# ESQUEMATICOS2.net
KiCad netlist of a schematic drawn in Altium Designer
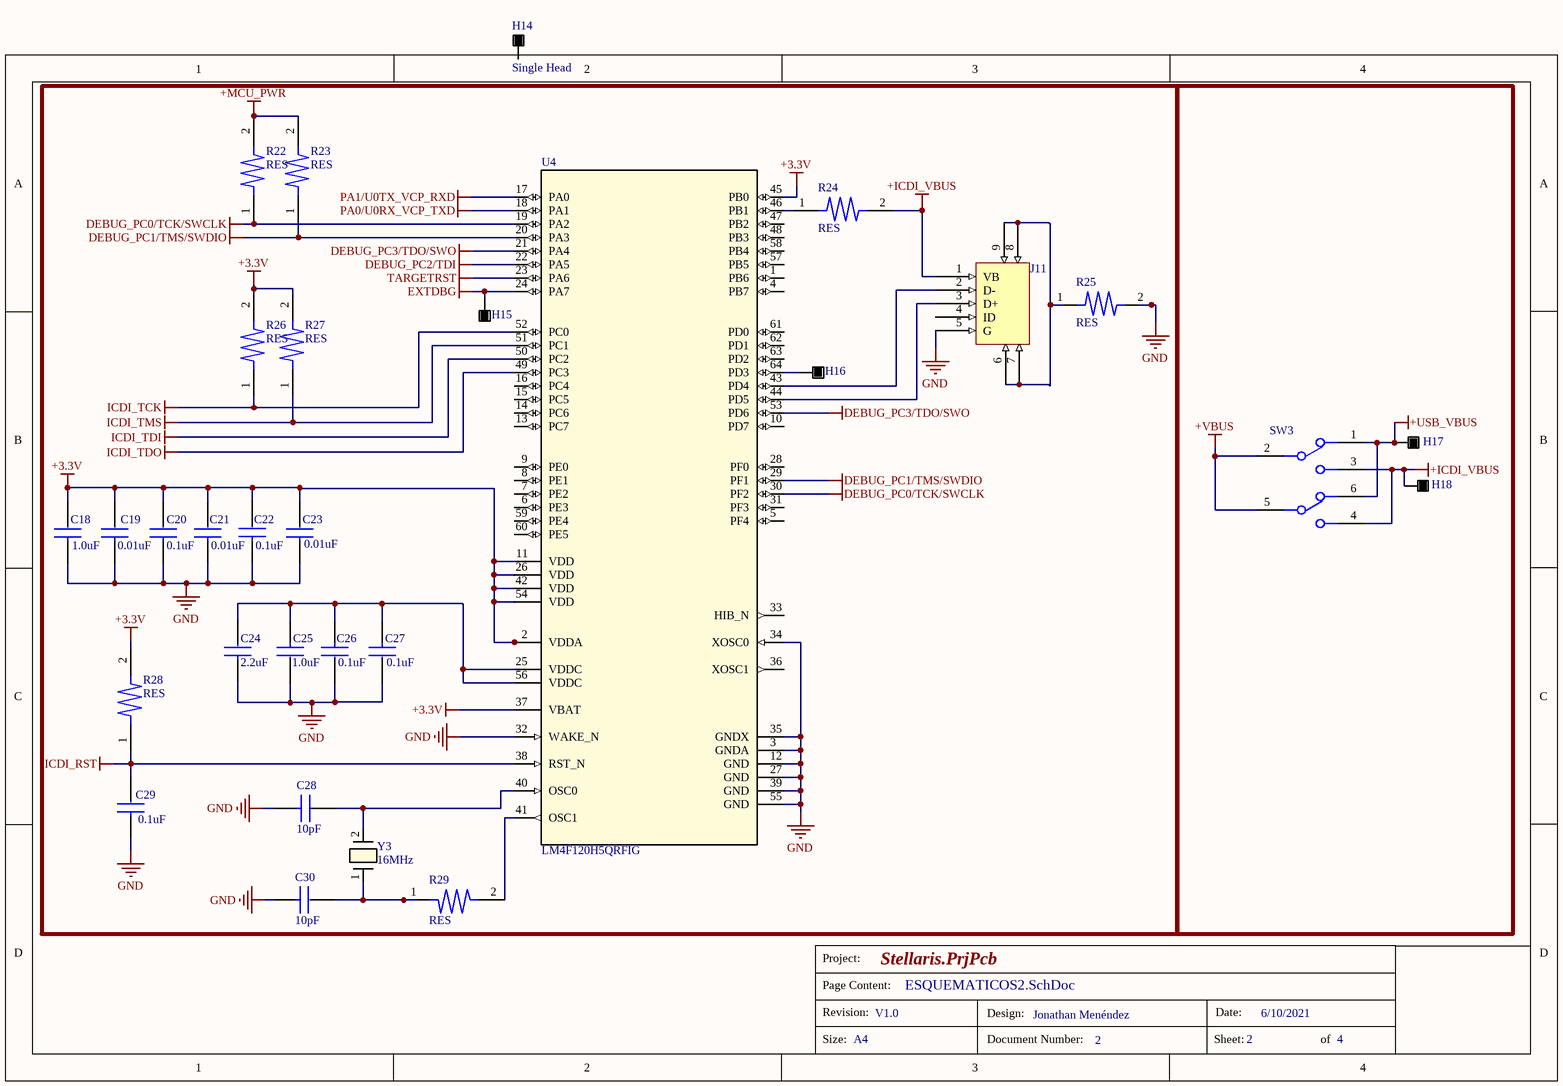
[diagram p0: ESQUEMATICOS2.SchDoc]

(export (version "E")
  (design (tool "Eeschema 10.0.6"))
  (components
    (comp (ref "C18")
      (value "1.0uF")
      (footprint "CAP 0402")
      (description "0402 0.1 uF 16 V ±10% Tolerance X7R Multilayer Ceramic Chip Capacitor")
      (fields
        (field (name "MANUFACTURER") "Taiyo Yuden")
        (field (name "MANUFACTURER PART NUMBER") "EMK105B7104KV-F")
      )
      (libsource (lib "Lib_componentes_Stellaris") (part "EMK105B7104KV-F"))
    )
    (comp (ref "C19")
      (value "0.01uF")
      (footprint "CAP 0402")
      (description "0402 0.01 uF 25 V ±10% X7R Automotive Multilayer Ceramic Capacitor")
      (fields
        (field (name "MANUFACTURER") "Taiyo Yuden")
        (field (name "MANUFACTURER PART NUMBER") "TMK105B7103KV-F")
      )
      (libsource (lib "Lib_componentes_Stellaris") (part "TMK105B7103KV-F"))
    )
    (comp (ref "C20")
      (value "0.1uF")
      (footprint "CAP 0402")
      (description "0402 0.1 uF 16 V ±10% Tolerance X7R Multilayer Ceramic Chip Capacitor")
      (fields
        (field (name "MANUFACTURER") "Taiyo Yuden")
        (field (name "MANUFACTURER PART NUMBER") "EMK105B7104KV-F")
      )
      (libsource (lib "Lib_componentes_Stellaris") (part "EMK105B7104KV-F"))
    )
    (comp (ref "C21")
      (value "0.01uF")
      (footprint "CAP 0402")
      (description "0402 0.01 uF 25 V ±10% X7R Automotive Multilayer Ceramic Capacitor")
      (fields
        (field (name "MANUFACTURER") "Taiyo Yuden")
        (field (name "MANUFACTURER PART NUMBER") "TMK105B7103KV-F")
      )
      (libsource (lib "Lib_componentes_Stellaris") (part "TMK105B7103KV-F"))
    )
    (comp (ref "C22")
      (value "0.1uF")
      (footprint "CAP 0402")
      (description "0402 0.1 uF 16 V ±10% Tolerance X7R Multilayer Ceramic Chip Capacitor")
      (fields
        (field (name "MANUFACTURER") "Taiyo Yuden")
        (field (name "MANUFACTURER PART NUMBER") "EMK105B7104KV-F")
      )
      (libsource (lib "Lib_componentes_Stellaris") (part "EMK105B7104KV-F"))
    )
    (comp (ref "C23")
      (value "0.01uF")
      (footprint "CAP 0402")
      (description "0402 0.01 uF 25 V ±10% X7R Automotive Multilayer Ceramic Capacitor")
      (fields
        (field (name "MANUFACTURER") "Taiyo Yuden")
        (field (name "MANUFACTURER PART NUMBER") "TMK105B7103KV-F")
      )
      (libsource (lib "Lib_componentes_Stellaris") (part "TMK105B7103KV-F"))
    )
    (comp (ref "C24")
      (value "2.2uF")
      (description "0603 2.2 uF 16 V ±10% Tolerance X5R SMT Multilayer Ceramic Capacitor")
      (fields
        (field (name "MANUFACTURER") "Murata")
        (field (name "MANUFACTURER PART NUMBER") "GRM188R61C225KE15D")
      )
      (libsource (lib "Lib_componentes_Stellaris") (part "GRM188R61C225KE15D"))
    )
    (comp (ref "C25")
      (value "1.0uF")
      (footprint "CAP 0402")
      (description "Multilayer Ceramic Capacitor, Tanceram Series, 1 - F, - 10%, X5R, 10 V, 0402 [1005 Metric]")
      (fields
        (field (name "MANUFACTURER") "Johanson")
        (field (name "MANUFACTURER PART NUMBER") "100R07X105KV4T")
      )
      (libsource (lib "Lib_componentes_Stellaris") (part "100R07X105KV4T"))
    )
    (comp (ref "C26")
      (value "0.1uF")
      (footprint "CAP 0402")
      (description "0402 0.1 uF 16 V ±10% Tolerance X7R Multilayer Ceramic Chip Capacitor")
      (fields
        (field (name "MANUFACTURER") "Taiyo Yuden")
        (field (name "MANUFACTURER PART NUMBER") "EMK105B7104KV-F")
      )
      (libsource (lib "Lib_componentes_Stellaris") (part "EMK105B7104KV-F"))
    )
    (comp (ref "C27")
      (value "0.1uF")
      (footprint "CAP 0402")
      (description "0402 0.1 uF 16 V ±10% Tolerance X7R Multilayer Ceramic Chip Capacitor")
      (fields
        (field (name "MANUFACTURER") "Taiyo Yuden")
        (field (name "MANUFACTURER PART NUMBER") "EMK105B7104KV-F")
      )
      (libsource (lib "Lib_componentes_Stellaris") (part "EMK105B7104KV-F"))
    )
    (comp (ref "C28")
      (value "10pF")
      (footprint "CAP 0402")
      (description "Cap Ceramic 10pF 50V C0G 5% SMD 0402 125°C Paper T/R")
      (fields
        (field (name "MANUFACTURER") "Murata")
        (field (name "MANUFACTURER PART NUMBER") "GRM1555C1H100JZ01D")
      )
      (libsource (lib "Lib_componentes_Stellaris") (part "GRM1555C1H100JZ01D"))
    )
    (comp (ref "C29")
      (value "0.1uF")
      (footprint "CAP 0402")
      (description "0402 0.1 uF 16 V ±10% Tolerance X7R Multilayer Ceramic Chip Capacitor")
      (fields
        (field (name "MANUFACTURER") "Taiyo Yuden")
        (field (name "MANUFACTURER PART NUMBER") "EMK105B7104KV-F")
      )
      (libsource (lib "Lib_componentes_Stellaris") (part "EMK105B7104KV-F"))
    )
    (comp (ref "C30")
      (value "10pF")
      (footprint "CAP 0402")
      (description "Cap Ceramic 10pF 50V C0G 5% SMD 0402 125°C Paper T/R")
      (fields
        (field (name "MANUFACTURER") "Murata")
        (field (name "MANUFACTURER PART NUMBER") "GRM1555C1H100JZ01D")
      )
      (libsource (lib "Lib_componentes_Stellaris") (part "GRM1555C1H100JZ01D"))
    )
    (comp (ref "H14")
      (value "Single Head")
      (footprint "Connector")
      (description "Connector")
      (libsource (lib "Lib_componentes_Stellaris") (part "Single Head"))
    )
    (comp (ref "H15")
      (value "Single Head")
      (footprint "Connector")
      (description "Connector")
      (libsource (lib "") (part "Single Head_2"))
    )
    (comp (ref "H16")
      (value "Single Head")
      (footprint "Connector")
      (description "Connector")
      (libsource (lib "") (part "Single Head_1"))
    )
    (comp (ref "H17")
      (value "Single Head")
      (footprint "Connector")
      (description "Connector")
      (libsource (lib "") (part "Single Head_1"))
    )
    (comp (ref "H18")
      (value "Single Head")
      (footprint "Connector")
      (description "Connector")
      (libsource (lib "") (part "Single Head_1"))
    )
    (comp (ref "J11")
      (value "ZX62-B-5PA(11)")
      (footprint "Micro USB 2.0 Type B")
      (description "Conn Micro USB 2.0 Type B RCP 5 POS 0.65mm Solder RA SMD 5 Terminal 1 Port T/R")
      (fields (field (name "MANUFACTURER") "Hirose"))
      (libsource (lib "Lib_componentes_Stellaris") (part "ZX62-B-5PA(11)"))
    )
    (comp (ref "R22")
      (value "RES")
      (footprint "RES 0402")
      (description "Res General Purpose Thick Film 0402 10K Ohm 1% 1/16W ±100ppm/°C Molded SMD Paper T/R")
      (fields
        (field (name "MANUFACTURER") "Yageo")
        (field (name "MANUFACTURER PART NUMBER") "RC0402FR-0710KL")
      )
      (libsource (lib "Comp_Stellaris") (part "RC0402FR-0710KL"))
    )
    (comp (ref "R23")
      (value "RES")
      (footprint "RES 0402")
      (description "Res General Purpose Thick Film 0402 10K Ohm 1% 1/16W ±100ppm/°C Molded SMD Paper T/R")
      (fields
        (field (name "MANUFACTURER") "Yageo")
        (field (name "MANUFACTURER PART NUMBER") "RC0402FR-0710KL")
      )
      (libsource (lib "Comp_Stellaris") (part "RC0402FR-0710KL"))
    )
    (comp (ref "R24")
      (value "RES")
      (footprint "RES 0402")
      (description "Res Thick Film 0402 330 Ohm 1% 0.063W(1/16W) ±100ppm/C Pad SMD T/R")
      (fields
        (field (name "MANUFACTURER") "Yageo")
        (field (name "MANUFACTURER PART NUMBER") "RC0402FR-07330RL")
      )
      (libsource (lib "Comp_Stellaris") (part "RC0402FR-07330RL"))
    )
    (comp (ref "R25")
      (value "RES")
      (footprint "RES 0603")
      (description "ERJ Series 0603 0 Ohm 0.1 W Jumper Surface Mount Thick Film Chip Resistor")
      (fields
        (field (name "MANUFACTURER") "Panasonic")
        (field (name "MANUFACTURER PART NUMBER") "ERJ-3GEY0R00V")
      )
      (libsource (lib "Comp_Stellaris") (part "ERJ-3GEY0R00V"))
    )
    (comp (ref "R26")
      (value "RES")
      (footprint "RES 0402")
      (description "Res General Purpose Thick Film 0402 10K Ohm 1% 1/16W ±100ppm/°C Molded SMD Paper T/R")
      (fields
        (field (name "MANUFACTURER") "Yageo")
        (field (name "MANUFACTURER PART NUMBER") "RC0402FR-0710KL")
      )
      (libsource (lib "Comp_Stellaris") (part "RC0402FR-0710KL"))
    )
    (comp (ref "R27")
      (value "RES")
      (footprint "RES 0402")
      (description "Res General Purpose Thick Film 0402 10K Ohm 1% 1/16W ±100ppm/°C Molded SMD Paper T/R")
      (fields
        (field (name "MANUFACTURER") "Yageo")
        (field (name "MANUFACTURER PART NUMBER") "RC0402FR-0710KL")
      )
      (libsource (lib "Comp_Stellaris") (part "RC0402FR-0710KL"))
    )
    (comp (ref "R28")
      (value "RES")
      (footprint "RES 0402")
      (description "Res General Purpose Thick Film 0402 10K Ohm 1% 1/16W ±100ppm/°C Molded SMD Paper T/R")
      (fields
        (field (name "MANUFACTURER") "Yageo")
        (field (name "MANUFACTURER PART NUMBER") "RC0402FR-0710KL")
      )
      (libsource (lib "Comp_Stellaris") (part "RC0402FR-0710KL"))
    )
    (comp (ref "R29")
      (value "RES")
      (footprint "RES 0603")
      (description "ERJ Series 0603 0 Ohm 0.1 W Jumper Surface Mount Thick Film Chip Resistor")
      (fields
        (field (name "MANUFACTURER") "Panasonic")
        (field (name "MANUFACTURER PART NUMBER") "ERJ-3GEY0R00V")
      )
      (libsource (lib "Comp_Stellaris") (part "ERJ-3GEY0R00V"))
    )
    (comp (ref "SW3")
      (value "JS202011SCQN")
      (footprint "JS202011SCQN")
      (description "C&k Components JS202011SCQN / Switch Slide DPDT 6VDC 0.3A SMT")
      (fields (field (name "MANUFACTURER") "ITT C&K"))
      (libsource (lib "Lib_componentes_Stellaris") (part "JS202011SCQN"))
    )
    (comp (ref "U4")
      (value "LM4F120H5QRFIG")
      (footprint "LM4F120H5QRFIG")
      (description "MCU 32-bit Stellaris ARM Cortex M4F RISC 256KB Flash 1.2V/3.3V 64-Pin LQFP Tray")
      (fields (field (name "MANUFACTURER") "Texas Instruments"))
      (libsource (lib "Comp_Stellaris") (part "LM4F120H5QRFIG"))
    )
    (comp (ref "Y3")
      (value "16MHz")
      (footprint "ABM3-16.000MHZ-B2-T")
      (description "Crystal 16MHz ±20ppm (Tol) ±50ppm (Stability) 18pF FUND 40Ohm 2-Pin Mini-CSMD T/R")
      (fields
        (field (name "MANUFACTURER") "Abracon")
        (field (name "MANUFACTURER PART NUMBER") "ABM3-16.000MHZ-B2-T")
      )
      (libsource (lib "Lib_componentes_Stellaris") (part "ABM3-16.000MHZ-B2-T"))
    )
  )
  (nets
    (net (code "1") (name "+3.3V") (class "Default")
      (node (ref "C18") (pin "2") (pinfunction "2_2") (pintype "passive"))
      (node (ref "C19") (pin "2") (pinfunction "2_2") (pintype "passive"))
      (node (ref "C20") (pin "2") (pinfunction "2_2") (pintype "passive"))
      (node (ref "C21") (pin "2") (pinfunction "2_2") (pintype "passive"))
      (node (ref "C22") (pin "2") (pinfunction "2_2") (pintype "passive"))
      (node (ref "C23") (pin "2") (pinfunction "2_2") (pintype "passive"))
      (node (ref "R26") (pin "2") (pinfunction "2_2") (pintype "passive"))
      (node (ref "R27") (pin "2") (pinfunction "2_2") (pintype "passive"))
      (node (ref "R28") (pin "2") (pinfunction "2_2") (pintype "passive"))
      (node (ref "U4") (pin "11") (pinfunction "VDD_11") (pintype "power_in"))
      (node (ref "U4") (pin "2") (pinfunction "VDDA_2") (pintype "power_in"))
      (node (ref "U4") (pin "26") (pinfunction "VDD_26") (pintype "power_in"))
      (node (ref "U4") (pin "37") (pinfunction "VBAT_37") (pintype "power_in"))
      (node (ref "U4") (pin "42") (pinfunction "VDD_42") (pintype "power_in"))
      (node (ref "U4") (pin "45") (pinfunction "PB0_45") (pintype "bidirectional"))
      (node (ref "U4") (pin "54") (pinfunction "VDD_54") (pintype "power_in"))
    )
    (net (code "2") (name "+ICDI_VBUS") (class "Default")
      (node (ref "H18") (pin "1") (pinfunction "1_1") (pintype "passive"))
      (node (ref "J11") (pin "1") (pinfunction "VB_1") (pintype "input"))
      (node (ref "R24") (pin "2") (pinfunction "2_2") (pintype "passive"))
      (node (ref "SW3") (pin "3") (pinfunction "3_3") (pintype "passive"))
      (node (ref "SW3") (pin "4") (pinfunction "4_4") (pintype "passive"))
    )
    (net (code "3") (name "+MCU_PWR") (class "Default")
      (node (ref "R22") (pin "2") (pinfunction "2_2") (pintype "passive"))
      (node (ref "R23") (pin "2") (pinfunction "2_2") (pintype "passive"))
    )
    (net (code "4") (name "+USB_VBUS") (class "Default")
      (node (ref "H17") (pin "1") (pinfunction "1_1") (pintype "passive"))
      (node (ref "SW3") (pin "1") (pinfunction "1_1") (pintype "passive"))
      (node (ref "SW3") (pin "6") (pinfunction "6_6") (pintype "passive"))
    )
    (net (code "5") (name "+VBUS") (class "Default")
      (node (ref "SW3") (pin "2") (pinfunction "2_2") (pintype "passive"))
      (node (ref "SW3") (pin "5") (pinfunction "5_5") (pintype "passive"))
    )
    (net (code "6") (name "DEBUG_PC0{slash}TCK{slash}SWCLK") (class "Default")
      (node (ref "R22") (pin "1") (pinfunction "1_1") (pintype "passive"))
      (node (ref "U4") (pin "19") (pinfunction "PA2_19") (pintype "bidirectional"))
      (node (ref "U4") (pin "30") (pinfunction "PF2_30") (pintype "bidirectional"))
    )
    (net (code "7") (name "DEBUG_PC1{slash}TMS{slash}SWDIO") (class "Default")
      (node (ref "R23") (pin "1") (pinfunction "1_1") (pintype "passive"))
      (node (ref "U4") (pin "20") (pinfunction "PA3_20") (pintype "bidirectional"))
      (node (ref "U4") (pin "29") (pinfunction "PF1_29") (pintype "bidirectional"))
    )
    (net (code "8") (name "DEBUG_PC2{slash}TDI") (class "Default")
      (node (ref "U4") (pin "22") (pinfunction "PA5_22") (pintype "bidirectional"))
    )
    (net (code "9") (name "DEBUG_PC3{slash}TDO{slash}SWO") (class "Default")
      (node (ref "U4") (pin "21") (pinfunction "PA4_21") (pintype "bidirectional"))
      (node (ref "U4") (pin "53") (pinfunction "PD6_53") (pintype "bidirectional"))
    )
    (net (code "10") (name "EXTDBG") (class "Default")
      (node (ref "H15") (pin "1") (pinfunction "1_1") (pintype "passive"))
      (node (ref "U4") (pin "24") (pinfunction "PA7_24") (pintype "bidirectional"))
    )
    (net (code "11") (name "GND") (class "Default")
      (node (ref "C18") (pin "1") (pinfunction "1_1") (pintype "passive"))
      (node (ref "C19") (pin "1") (pinfunction "1_1") (pintype "passive"))
      (node (ref "C20") (pin "1") (pinfunction "1_1") (pintype "passive"))
      (node (ref "C21") (pin "1") (pinfunction "1_1") (pintype "passive"))
      (node (ref "C22") (pin "1") (pinfunction "1_1") (pintype "passive"))
      (node (ref "C23") (pin "1") (pinfunction "1_1") (pintype "passive"))
      (node (ref "C24") (pin "1") (pinfunction "1_1") (pintype "passive"))
      (node (ref "C25") (pin "2") (pinfunction "2_2") (pintype "passive"))
      (node (ref "C26") (pin "2") (pinfunction "2_2") (pintype "passive"))
      (node (ref "C27") (pin "2") (pinfunction "2_2") (pintype "passive"))
      (node (ref "C28") (pin "1") (pinfunction "1_1") (pintype "passive"))
      (node (ref "C29") (pin "1") (pinfunction "1_1") (pintype "passive"))
      (node (ref "C30") (pin "1") (pinfunction "1_1") (pintype "passive"))
      (node (ref "J11") (pin "5") (pinfunction "G_5") (pintype "input"))
      (node (ref "R25") (pin "2") (pinfunction "2_2") (pintype "passive"))
      (node (ref "U4") (pin "12") (pinfunction "GND_12") (pintype "power_in"))
      (node (ref "U4") (pin "27") (pinfunction "GND_27") (pintype "power_in"))
      (node (ref "U4") (pin "3") (pinfunction "GNDA_3") (pintype "power_in"))
      (node (ref "U4") (pin "32") (pinfunction "WAKE_N_32") (pintype "input"))
      (node (ref "U4") (pin "34") (pinfunction "XOSC0_34") (pintype "input"))
      (node (ref "U4") (pin "35") (pinfunction "GNDX_35") (pintype "power_in"))
      (node (ref "U4") (pin "39") (pinfunction "GND_39") (pintype "power_in"))
      (node (ref "U4") (pin "55") (pinfunction "GND_55") (pintype "power_in"))
    )
    (net (code "12") (name "ICDI_RST") (class "Default")
      (node (ref "C29") (pin "2") (pinfunction "2_2") (pintype "passive"))
      (node (ref "R28") (pin "1") (pinfunction "1_1") (pintype "passive"))
      (node (ref "U4") (pin "38") (pinfunction "RST_N_38") (pintype "input"))
    )
    (net (code "13") (name "ICDI_TCK") (class "Default")
      (node (ref "R26") (pin "1") (pinfunction "1_1") (pintype "passive"))
      (node (ref "U4") (pin "52") (pinfunction "PC0_52") (pintype "bidirectional"))
    )
    (net (code "14") (name "ICDI_TDI") (class "Default")
      (node (ref "U4") (pin "50") (pinfunction "PC2_50") (pintype "bidirectional"))
    )
    (net (code "15") (name "ICDI_TDO") (class "Default")
      (node (ref "U4") (pin "49") (pinfunction "PC3_49") (pintype "bidirectional"))
    )
    (net (code "16") (name "ICDI_TMS") (class "Default")
      (node (ref "R27") (pin "1") (pinfunction "1_1") (pintype "passive"))
      (node (ref "U4") (pin "51") (pinfunction "PC1_51") (pintype "bidirectional"))
    )
    (net (code "17") (name "Net-(C24-Pad2)") (class "Default")
      (node (ref "C24") (pin "2") (pinfunction "2_2") (pintype "passive"))
      (node (ref "C25") (pin "1") (pinfunction "1_1") (pintype "passive"))
      (node (ref "C26") (pin "1") (pinfunction "1_1") (pintype "passive"))
      (node (ref "C27") (pin "1") (pinfunction "1_1") (pintype "passive"))
      (node (ref "U4") (pin "25") (pinfunction "VDDC_25") (pintype "power_in"))
      (node (ref "U4") (pin "56") (pinfunction "VDDC_56") (pintype "power_in"))
    )
    (net (code "18") (name "Net-(C30-Pad2)") (class "Default")
      (node (ref "C30") (pin "2") (pinfunction "2_2") (pintype "passive"))
      (node (ref "R29") (pin "1") (pinfunction "1_1") (pintype "passive"))
      (node (ref "Y3") (pin "1") (pinfunction "1_1") (pintype "passive"))
    )
    (net (code "19") (name "Net-(J11-D+)") (class "Default")
      (node (ref "J11") (pin "3") (pinfunction "D+_3") (pintype "input"))
      (node (ref "U4") (pin "44") (pinfunction "PD5_44") (pintype "bidirectional"))
    )
    (net (code "20") (name "Net-(J11-D-)") (class "Default")
      (node (ref "J11") (pin "2") (pinfunction "D-_2") (pintype "input"))
      (node (ref "U4") (pin "43") (pinfunction "PD4_43") (pintype "bidirectional"))
    )
    (net (code "21") (name "Net-(J11-Pad6)") (class "Default")
      (node (ref "J11") (pin "6") (pintype "input"))
      (node (ref "J11") (pin "7") (pintype "input"))
      (node (ref "J11") (pin "8") (pintype "input"))
      (node (ref "J11") (pin "9") (pintype "input"))
      (node (ref "R25") (pin "1") (pinfunction "1_1") (pintype "passive"))
    )
    (net (code "22") (name "Net-(U4-OSC0)") (class "Default")
      (node (ref "C28") (pin "2") (pinfunction "2_2") (pintype "passive"))
      (node (ref "U4") (pin "40") (pinfunction "OSC0_40") (pintype "input"))
      (node (ref "Y3") (pin "2") (pinfunction "2_2") (pintype "passive"))
    )
    (net (code "23") (name "Net-(U4-OSC1)") (class "Default")
      (node (ref "R29") (pin "2") (pinfunction "2_2") (pintype "passive"))
      (node (ref "U4") (pin "41") (pinfunction "OSC1_41") (pintype "output"))
    )
    (net (code "24") (name "Net-(U4-PB1)") (class "Default")
      (node (ref "R24") (pin "1") (pinfunction "1_1") (pintype "passive"))
      (node (ref "U4") (pin "46") (pinfunction "PB1_46") (pintype "bidirectional"))
    )
    (net (code "25") (name "Net-(U4-PD3)") (class "Default")
      (node (ref "H16") (pin "1") (pinfunction "1_1") (pintype "passive"))
      (node (ref "U4") (pin "64") (pinfunction "PD3_64") (pintype "bidirectional"))
    )
    (net (code "26") (name "PA0{slash}U0RX_VCP_TXD") (class "Default")
      (node (ref "U4") (pin "18") (pinfunction "PA1_18") (pintype "bidirectional"))
    )
    (net (code "27") (name "PA1{slash}U0TX_VCP_RXD") (class "Default")
      (node (ref "U4") (pin "17") (pinfunction "PA0_17") (pintype "bidirectional"))
    )
    (net (code "28") (name "TARGETRST") (class "Default")
      (node (ref "U4") (pin "23") (pinfunction "PA6_23") (pintype "bidirectional"))
    )
    (net (code "29") (name "unconnected-(H14-Pad1)") (class "Default")
      (node (ref "H14") (pin "1") (pinfunction "1_1") (pintype "passive"))
    )
    (net (code "30") (name "unconnected-(J11-ID-Pad4)") (class "Default")
      (node (ref "J11") (pin "4") (pinfunction "ID_4") (pintype "input"))
    )
    (net (code "31") (name "unconnected-(U4-HIB_N-Pad33)") (class "Default")
      (node (ref "U4") (pin "33") (pinfunction "HIB_N_33") (pintype "output"))
    )
    (net (code "32") (name "unconnected-(U4-PB2-Pad47)") (class "Default")
      (node (ref "U4") (pin "47") (pinfunction "PB2_47") (pintype "bidirectional"))
    )
    (net (code "33") (name "unconnected-(U4-PB3-Pad48)") (class "Default")
      (node (ref "U4") (pin "48") (pinfunction "PB3_48") (pintype "bidirectional"))
    )
    (net (code "34") (name "unconnected-(U4-PB4-Pad58)") (class "Default")
      (node (ref "U4") (pin "58") (pinfunction "PB4_58") (pintype "bidirectional"))
    )
    (net (code "35") (name "unconnected-(U4-PB5-Pad57)") (class "Default")
      (node (ref "U4") (pin "57") (pinfunction "PB5_57") (pintype "bidirectional"))
    )
    (net (code "36") (name "unconnected-(U4-PB6-Pad1)") (class "Default")
      (node (ref "U4") (pin "1") (pinfunction "PB6_1") (pintype "bidirectional"))
    )
    (net (code "37") (name "unconnected-(U4-PB7-Pad4)") (class "Default")
      (node (ref "U4") (pin "4") (pinfunction "PB7_4") (pintype "bidirectional"))
    )
    (net (code "38") (name "unconnected-(U4-PC4-Pad16)") (class "Default")
      (node (ref "U4") (pin "16") (pinfunction "PC4_16") (pintype "bidirectional"))
    )
    (net (code "39") (name "unconnected-(U4-PC5-Pad15)") (class "Default")
      (node (ref "U4") (pin "15") (pinfunction "PC5_15") (pintype "bidirectional"))
    )
    (net (code "40") (name "unconnected-(U4-PC6-Pad14)") (class "Default")
      (node (ref "U4") (pin "14") (pinfunction "PC6_14") (pintype "bidirectional"))
    )
    (net (code "41") (name "unconnected-(U4-PC7-Pad13)") (class "Default")
      (node (ref "U4") (pin "13") (pinfunction "PC7_13") (pintype "bidirectional"))
    )
    (net (code "42") (name "unconnected-(U4-PD0-Pad61)") (class "Default")
      (node (ref "U4") (pin "61") (pinfunction "PD0_61") (pintype "bidirectional"))
    )
    (net (code "43") (name "unconnected-(U4-PD1-Pad62)") (class "Default")
      (node (ref "U4") (pin "62") (pinfunction "PD1_62") (pintype "bidirectional"))
    )
    (net (code "44") (name "unconnected-(U4-PD2-Pad63)") (class "Default")
      (node (ref "U4") (pin "63") (pinfunction "PD2_63") (pintype "bidirectional"))
    )
    (net (code "45") (name "unconnected-(U4-PD7-Pad10)") (class "Default")
      (node (ref "U4") (pin "10") (pinfunction "PD7_10") (pintype "bidirectional"))
    )
    (net (code "46") (name "unconnected-(U4-PE0-Pad9)") (class "Default")
      (node (ref "U4") (pin "9") (pinfunction "PE0_9") (pintype "bidirectional"))
    )
    (net (code "47") (name "unconnected-(U4-PE1-Pad8)") (class "Default")
      (node (ref "U4") (pin "8") (pinfunction "PE1_8") (pintype "bidirectional"))
    )
    (net (code "48") (name "unconnected-(U4-PE2-Pad7)") (class "Default")
      (node (ref "U4") (pin "7") (pinfunction "PE2_7") (pintype "bidirectional"))
    )
    (net (code "49") (name "unconnected-(U4-PE3-Pad6)") (class "Default")
      (node (ref "U4") (pin "6") (pinfunction "PE3_6") (pintype "bidirectional"))
    )
    (net (code "50") (name "unconnected-(U4-PE4-Pad59)") (class "Default")
      (node (ref "U4") (pin "59") (pinfunction "PE4_59") (pintype "bidirectional"))
    )
    (net (code "51") (name "unconnected-(U4-PE5-Pad60)") (class "Default")
      (node (ref "U4") (pin "60") (pinfunction "PE5_60") (pintype "bidirectional"))
    )
    (net (code "52") (name "unconnected-(U4-PF0-Pad28)") (class "Default")
      (node (ref "U4") (pin "28") (pinfunction "PF0_28") (pintype "bidirectional"))
    )
    (net (code "53") (name "unconnected-(U4-PF3-Pad31)") (class "Default")
      (node (ref "U4") (pin "31") (pinfunction "PF3_31") (pintype "bidirectional"))
    )
    (net (code "54") (name "unconnected-(U4-PF4-Pad5)") (class "Default")
      (node (ref "U4") (pin "5") (pinfunction "PF4_5") (pintype "bidirectional"))
    )
    (net (code "55") (name "unconnected-(U4-XOSC1-Pad36)") (class "Default")
      (node (ref "U4") (pin "36") (pinfunction "XOSC1_36") (pintype "output"))
    )
  )
)
